# CanRotor_Mini_2.net
KiCad netlist of a schematic drawn in Altium Designer
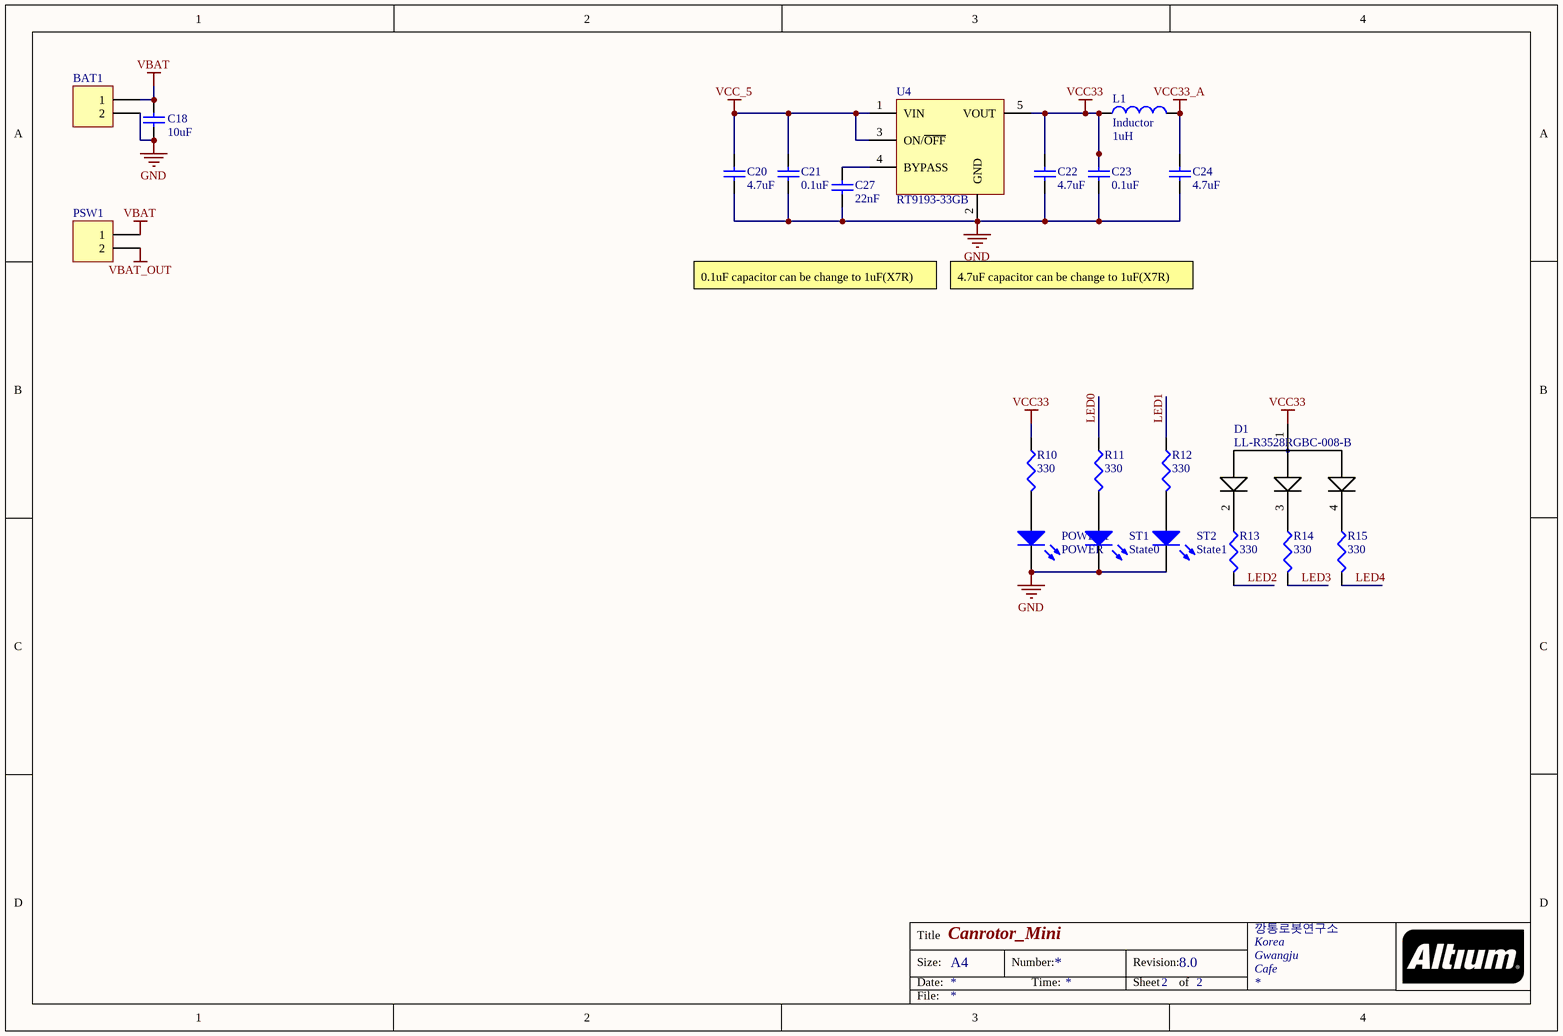
[diagram p0: CanRotor_Mini(2).SchDoc]

(export (version "E")
  (design (tool "Eeschema 10.0.6"))
  (components
    (comp (ref "BAT1")
      (value "Header 2")
      (footprint "HDR1X2")
      (description "Header, 2-Pin")
      (fields (field (name "PUBLISHER") "Altium Limited"))
      (libsource (lib "Miscellaneous Connectors") (part "Header 2"))
    )
    (comp (ref "C18")
      (value "10uF")
      (footprint "C1206")
      (description "Capacitor (Semiconductor SIM Model)")
      (fields (field (name "Comment") "Cap Semi") (field (name "PUBLISHER") "Altium Limited"))
      (libsource (lib "Miscellaneous Devices") (part "Cap Semi"))
    )
    (comp (ref "C20")
      (value "4.7uF")
      (footprint "C1206")
      (description "Capacitor (Semiconductor SIM Model)")
      (fields (field (name "Comment") "Cap Semi") (field (name "PUBLISHER") "Altium Limited"))
      (libsource (lib "Miscellaneous Devices") (part "Cap Semi"))
    )
    (comp (ref "C21")
      (value "0.1uF")
      (footprint "1608[0603]")
      (description "Capacitor (Semiconductor SIM Model)")
      (fields (field (name "Comment") "Cap Semi") (field (name "PUBLISHER") "Altium Limited"))
      (libsource (lib "Miscellaneous Devices") (part "Cap Semi"))
    )
    (comp (ref "C22")
      (value "4.7uF")
      (footprint "6-0805_L")
      (description "Capacitor (Semiconductor SIM Model)")
      (fields (field (name "Comment") "Cap Semi") (field (name "PUBLISHER") "Altium Limited"))
      (libsource (lib "Miscellaneous Devices") (part "Cap Semi"))
    )
    (comp (ref "C23")
      (value "0.1uF")
      (footprint "1608[0603]")
      (description "Capacitor (Semiconductor SIM Model)")
      (fields (field (name "Comment") "Cap Semi") (field (name "PUBLISHER") "Altium Limited"))
      (libsource (lib "Miscellaneous Devices") (part "Cap Semi"))
    )
    (comp (ref "C24")
      (value "4.7uF")
      (footprint "6-0805_L")
      (description "Capacitor (Semiconductor SIM Model)")
      (fields (field (name "Comment") "Cap Semi") (field (name "PUBLISHER") "Altium Limited"))
      (libsource (lib "Miscellaneous Devices") (part "Cap Semi"))
    )
    (comp (ref "C27")
      (value "22nF")
      (footprint "1608[0603]")
      (description "Capacitor (Semiconductor SIM Model)")
      (fields (field (name "Comment") "Cap Semi") (field (name "PUBLISHER") "Altium Limited"))
      (libsource (lib "Miscellaneous Devices") (part "Cap Semi"))
    )
    (comp (ref "D1")
      (value "LL-R3528RGBC-008-B")
      (footprint "LED_LL-R3528RGBC-008-B")
      (description "LED; SMD; 3528, PLCC2; RGB; 3.5x2.8mm; 120째; Red lumin: 1")
      (fields (field (name "MF") "Lucky Light"))
      (libsource (lib "LL-R3528RGBC-008-B") (part "LL-R3528RGBC-008-B"))
    )
    (comp (ref "L1")
      (value "Inductor")
      (footprint "1608[0603]")
      (fields (field (name "ALTIUM_VALUE") "1uH") (field (name "PUBLISHER") "Altium Limited"))
      (libsource (lib "Miscellaneous Devices") (part "Inductor"))
    )
    (comp (ref "POWER1")
      (value "POWER")
      (footprint "LED0603")
      (description "Typical RED, GREEN, YELLOW, AMBER GaAs LED")
      (fields (field (name "PUBLISHER") "Altium Limited"))
      (libsource (lib "Miscellaneous Devices") (part "LED2"))
    )
    (comp (ref "PSW1")
      (value "Header 2")
      (footprint "HDR1X2")
      (description "Header, 2-Pin")
      (fields (field (name "PUBLISHER") "Altium Limited"))
      (libsource (lib "Miscellaneous Connectors") (part "Header 2"))
    )
    (comp (ref "R10")
      (value "330")
      (footprint "J1-0603")
      (description "Resistor")
      (fields (field (name "Comment") "Res3") (field (name "PUBLISHER") "Altium Limited"))
      (libsource (lib "Miscellaneous Devices") (part "Res3"))
    )
    (comp (ref "R11")
      (value "330")
      (footprint "J1-0603")
      (description "Resistor")
      (fields (field (name "Comment") "Res3") (field (name "PUBLISHER") "Altium Limited"))
      (libsource (lib "Miscellaneous Devices") (part "Res3"))
    )
    (comp (ref "R12")
      (value "330")
      (footprint "J1-0603")
      (description "Resistor")
      (fields (field (name "Comment") "Res3") (field (name "PUBLISHER") "Altium Limited"))
      (libsource (lib "Miscellaneous Devices") (part "Res3"))
    )
    (comp (ref "R13")
      (value "330")
      (footprint "J1-0603")
      (description "Resistor")
      (fields (field (name "Comment") "Res3") (field (name "PUBLISHER") "Altium Limited"))
      (libsource (lib "Miscellaneous Devices") (part "Res3"))
    )
    (comp (ref "R14")
      (value "330")
      (footprint "J1-0603")
      (description "Resistor")
      (fields (field (name "Comment") "Res3") (field (name "PUBLISHER") "Altium Limited"))
      (libsource (lib "Miscellaneous Devices") (part "Res3"))
    )
    (comp (ref "R15")
      (value "330")
      (footprint "J1-0603")
      (description "Resistor")
      (fields (field (name "Comment") "Res3") (field (name "PUBLISHER") "Altium Limited"))
      (libsource (lib "Miscellaneous Devices") (part "Res3"))
    )
    (comp (ref "ST1")
      (value "State0")
      (footprint "LED0603")
      (description "Typical RED, GREEN, YELLOW, AMBER GaAs LED")
      (fields (field (name "PUBLISHER") "Altium Limited"))
      (libsource (lib "Miscellaneous Devices") (part "LED2"))
    )
    (comp (ref "ST2")
      (value "State1")
      (footprint "LED0603")
      (description "Typical RED, GREEN, YELLOW, AMBER GaAs LED")
      (fields (field (name "PUBLISHER") "Altium Limited"))
      (libsource (lib "Miscellaneous Devices") (part "LED2"))
    )
    (comp (ref "U4")
      (value "RT9193-33GB")
      (footprint "SOT-23-5")
      (libsource (lib "RT9193-33GB") (part "RT9193-33GB"))
    )
  )
  (nets
    (net (code "1") (name "/LED0") (class "Default")
      (node (ref "R11") (pin "1") (pinfunction "1_1") (pintype "passive"))
    )
    (net (code "2") (name "/LED1") (class "Default")
      (node (ref "R12") (pin "1") (pinfunction "1_1") (pintype "passive"))
    )
    (net (code "3") (name "/LED2") (class "Default")
      (node (ref "R13") (pin "2") (pinfunction "2_2") (pintype "passive"))
    )
    (net (code "4") (name "/LED3") (class "Default")
      (node (ref "R14") (pin "2") (pinfunction "2_2") (pintype "passive"))
    )
    (net (code "5") (name "/LED4") (class "Default")
      (node (ref "R15") (pin "2") (pinfunction "2_2") (pintype "passive"))
    )
    (net (code "6") (name "GND") (class "Default")
      (node (ref "BAT1") (pin "2") (pinfunction "2_2") (pintype "passive"))
      (node (ref "C18") (pin "2") (pinfunction "2_2") (pintype "passive"))
      (node (ref "C20") (pin "2") (pinfunction "2_2") (pintype "passive"))
      (node (ref "C21") (pin "2") (pinfunction "2_2") (pintype "passive"))
      (node (ref "C22") (pin "2") (pinfunction "2_2") (pintype "passive"))
      (node (ref "C23") (pin "2") (pinfunction "2_2") (pintype "passive"))
      (node (ref "C24") (pin "2") (pinfunction "2_2") (pintype "passive"))
      (node (ref "C27") (pin "2") (pinfunction "2_2") (pintype "passive"))
      (node (ref "POWER1") (pin "2") (pinfunction "K_2") (pintype "passive"))
      (node (ref "ST1") (pin "2") (pinfunction "K_2") (pintype "passive"))
      (node (ref "ST2") (pin "2") (pinfunction "K_2") (pintype "passive"))
      (node (ref "U4") (pin "2") (pinfunction "GND_2") (pintype "power_in"))
    )
    (net (code "7") (name "Net-(D1-CATHODE_BLUE)") (class "Default")
      (node (ref "D1") (pin "4") (pinfunction "CATHODE_BLUE_4") (pintype "passive"))
      (node (ref "R15") (pin "1") (pinfunction "1_1") (pintype "passive"))
    )
    (net (code "8") (name "Net-(D1-CATHODE_GREEN)") (class "Default")
      (node (ref "D1") (pin "3") (pinfunction "CATHODE_GREEN_3") (pintype "passive"))
      (node (ref "R14") (pin "1") (pinfunction "1_1") (pintype "passive"))
    )
    (net (code "9") (name "Net-(D1-CATHODE_RED)") (class "Default")
      (node (ref "D1") (pin "2") (pinfunction "CATHODE_RED_2") (pintype "passive"))
      (node (ref "R13") (pin "1") (pinfunction "1_1") (pintype "passive"))
    )
    (net (code "10") (name "Net-(POWER1-A)") (class "Default")
      (node (ref "POWER1") (pin "1") (pinfunction "A_1") (pintype "passive"))
      (node (ref "R10") (pin "2") (pinfunction "2_2") (pintype "passive"))
    )
    (net (code "11") (name "Net-(ST1-A)") (class "Default")
      (node (ref "R11") (pin "2") (pinfunction "2_2") (pintype "passive"))
      (node (ref "ST1") (pin "1") (pinfunction "A_1") (pintype "passive"))
    )
    (net (code "12") (name "Net-(ST2-A)") (class "Default")
      (node (ref "R12") (pin "2") (pinfunction "2_2") (pintype "passive"))
      (node (ref "ST2") (pin "1") (pinfunction "A_1") (pintype "passive"))
    )
    (net (code "13") (name "Net-(U4-BYPASS)") (class "Default")
      (node (ref "C27") (pin "1") (pinfunction "1_1") (pintype "passive"))
      (node (ref "U4") (pin "4") (pinfunction "BYPASS_4") (pintype "passive"))
    )
    (net (code "14") (name "VBAT") (class "Default")
      (node (ref "BAT1") (pin "1") (pinfunction "1_1") (pintype "passive"))
      (node (ref "C18") (pin "1") (pinfunction "1_1") (pintype "passive"))
      (node (ref "PSW1") (pin "1") (pinfunction "1_1") (pintype "passive"))
    )
    (net (code "15") (name "VBAT_OUT") (class "Default")
      (node (ref "PSW1") (pin "2") (pinfunction "2_2") (pintype "passive"))
    )
    (net (code "16") (name "VCC33") (class "Default")
      (node (ref "C22") (pin "1") (pinfunction "1_1") (pintype "passive"))
      (node (ref "C23") (pin "1") (pinfunction "1_1") (pintype "passive"))
      (node (ref "D1") (pin "1") (pinfunction "COMM_ANODE_1") (pintype "passive"))
      (node (ref "L1") (pin "1") (pinfunction "1_1") (pintype "passive"))
      (node (ref "R10") (pin "1") (pinfunction "1_1") (pintype "passive"))
      (node (ref "U4") (pin "5") (pinfunction "VOUT_5") (pintype "power_in"))
    )
    (net (code "17") (name "VCC33_A") (class "Default")
      (node (ref "C24") (pin "1") (pinfunction "1_1") (pintype "passive"))
      (node (ref "L1") (pin "2") (pinfunction "2_2") (pintype "passive"))
    )
    (net (code "18") (name "VCC_5") (class "Default")
      (node (ref "C20") (pin "1") (pinfunction "1_1") (pintype "passive"))
      (node (ref "C21") (pin "1") (pinfunction "1_1") (pintype "passive"))
      (node (ref "U4") (pin "1") (pinfunction "VIN_1") (pintype "power_in"))
      (node (ref "U4") (pin "3") (pinfunction "ON/~{OFF}_3") (pintype "passive"))
    )
  )
)
